# USB.net
KiCad netlist of a schematic drawn in Altium Designer
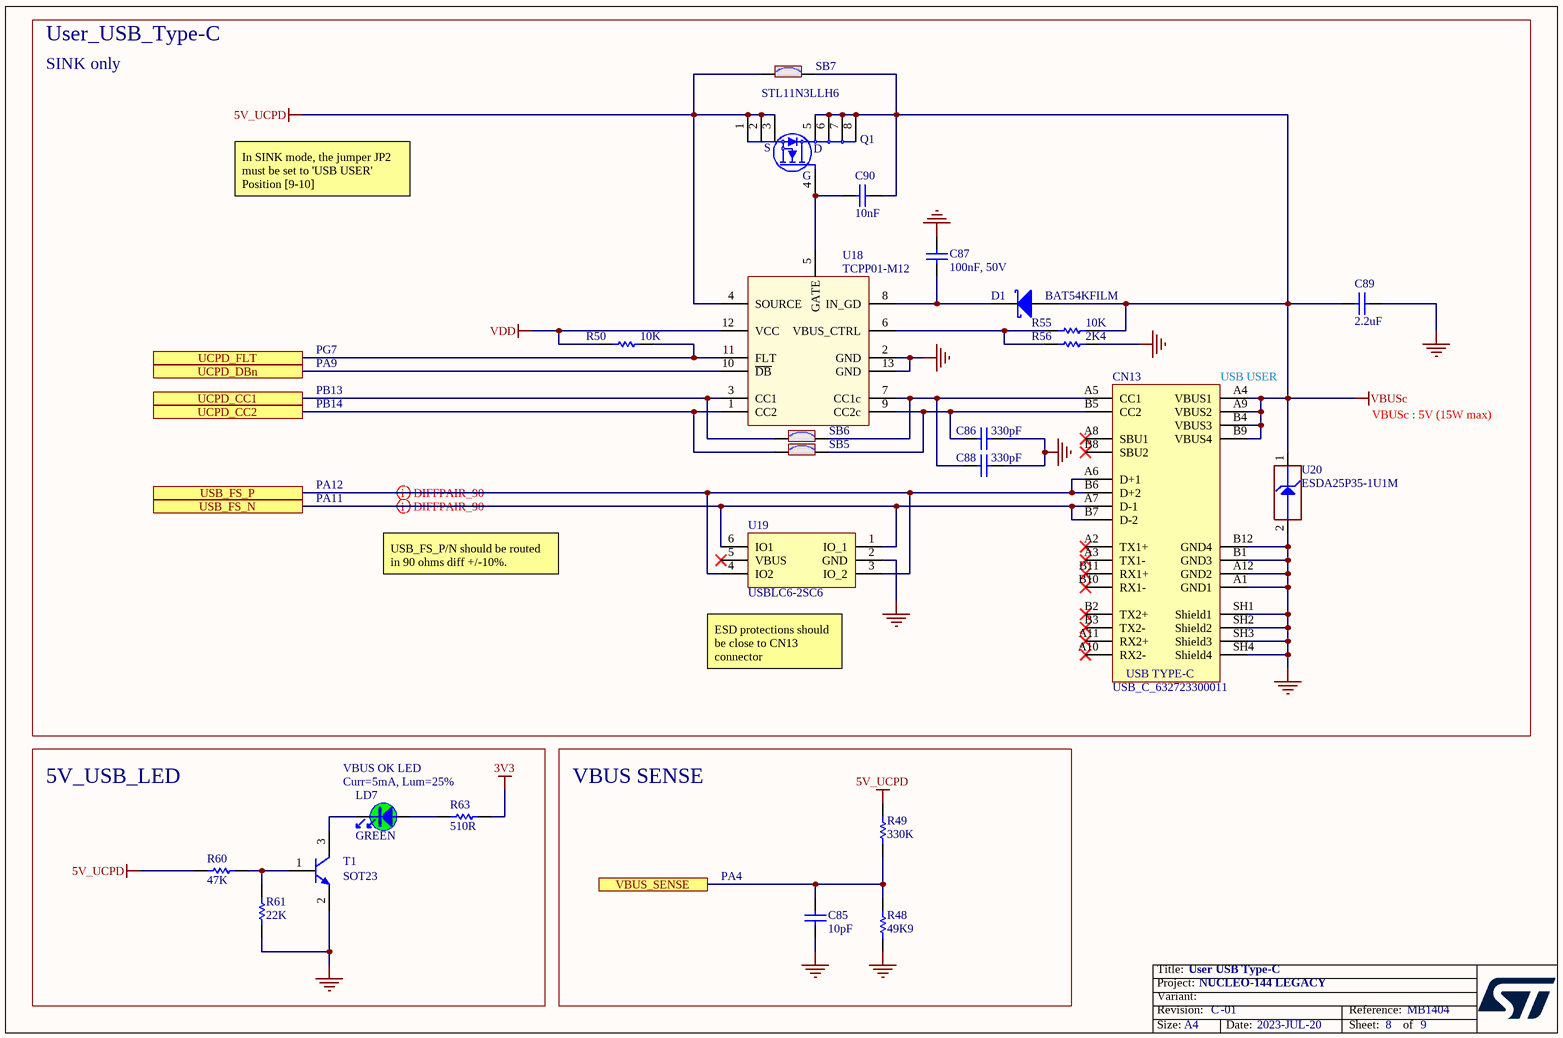
[diagram p0: USB.SchDoc]

(export (version "E")
  (design (tool "Eeschema 10.0.6"))
  (components
    (comp (ref "C85")
      (value "10pF")
      (footprint "MCD_PARTS:C0603")
      (description "Capacitor, MLCC, 10pF, 50V, NPO, 5%, 0603, T=0,8mm")
      (fields
        (field (name "INTERNAL_PART_NUMBER") "MCD-00637")
        (field (name "MANUFACTURER_PART_NUMBER") "CC0603JRNPO9BN100")
        (field (name "PROVIDED_BY") "SUBCO")
      )
      (libsource (lib "MCD_PARTS_database") (part "Capacitor"))
    )
    (comp (ref "C86")
      (value "330pF")
      (footprint "MCD_PARTS:C0402")
      (description "Capacitor, MLCC, 330pF, 50V, NPO, +/-5%, 0402, T=0,5mm")
      (fields (field (name "INTERNAL_PART_NUMBER") "MCD-01579") (field (name "MANUFACTURER") "YAGEO"))
      (libsource (lib "MCD_PARTS_database") (part "Capacitor"))
    )
    (comp (ref "C87")
      (value "100nF, 50V")
      (footprint "MCD_PARTS:C0603")
      (description "Capacitor,100nF,50V,X7R,10%,0603")
      (fields
        (field (name "INTERNAL_PART_NUMBER") "MCD-01099")
        (field (name "MANUFACTURER_PART_NUMBER") "CC0603KRX7R9BB104")
        (field (name "PROVIDED_BY") "SUBCO")
      )
      (libsource (lib "MCD_PARTS_database") (part "Capacitor"))
    )
    (comp (ref "C88")
      (value "330pF")
      (footprint "MCD_PARTS:C0402")
      (description "Capacitor, MLCC, 330pF, 50V, NPO, +/-5%, 0402, T=0,5mm")
      (fields (field (name "INTERNAL_PART_NUMBER") "MCD-01579") (field (name "MANUFACTURER") "YAGEO"))
      (libsource (lib "MCD_PARTS_database") (part "Capacitor"))
    )
    (comp (ref "C89")
      (value "2.2uF")
      (footprint "MCD_PARTS:C0805")
      (description "Capacitor, MLCC, 2.2uF, 25V, X7R, +/-10%, 0805, T=1,25mm")
      (fields (field (name "INTERNAL_PART_NUMBER") "MCD-02372") (field (name "MANUFACTURER") "MURATA"))
      (libsource (lib "MCD_PARTS_database") (part "Capacitor"))
    )
    (comp (ref "C90")
      (value "10nF")
      (footprint "MCD_PARTS:C0402")
      (description "Capacitor, MLCC, 10nF, 50V ,X7R, +/-10%, 0402, T=0.5mm")
      (fields (field (name "INTERNAL_PART_NUMBER") "MCD-02198") (field (name "MANUFACTURER") "YAGEO"))
      (libsource (lib "MCD_PARTS_database") (part "Capacitor"))
    )
    (comp (ref "CN13")
      (value "USB_C_632723300011")
      (footprint "MCD_PARTS:CON_USB-TYPEC_WE_632723300011")
      (description "Connector_USB_TypeC, 24pins, RA, TH, T=1.9mm (USB certified)")
      (fields
        (field (name "INTERNAL_PART_NUMBER") "MCD-02273")
        (field (name "MANUFACTURER") "WURTH ELEKTRONIK")
      )
      (libsource (lib "MCD_PARTS_database") (part "USB_TYPE_C_Receptacle"))
    )
    (comp (ref "D1")
      (value "BAT54KFILM")
      (footprint "MCD_PARTS:DIO_SOD523_1A_2K")
      (description "Small signal Schottky diodes")
      (fields
        (field (name "INTERNAL_PART_NUMBER") "MCD-01677")
        (field (name "MANUFACTURER") "STMICROELECTRONICS")
        (field (name "PROVIDED_BY") "SUBCO")
      )
      (libsource (lib "MCD_PARTS_database") (part "SCHOTTKY_1A_2K"))
    )
    (comp (ref "LD7")
      (value "GREEN")
      (footprint "MCD_PARTS:LED_0603_OSRAM_LG-Q396-PS-35_GREEN_1A2K_H0P4")
      (description "LED Green, 0603 SMD, Forward Voltage Typ=2V, Max=2.5V")
      (fields
        (field (name "INTERNAL_PART_NUMBER") "MCD-00588")
        (field (name "MANUFACTURER_PART_NUMBER") "LG Q396-PS-35")
        (field (name "PROVIDED_BY") "SUBCO")
      )
      (libsource (lib "MCD_PARTS_database") (part "LED_green"))
    )
    (comp (ref "Q1")
      (value "STL11N3LLH6")
      (footprint "MCD_PARTS:MOS_POWERFLAT_3P3X3P3_P065")
      (description "N-channel 30 V, 6 mΩ typ, 11 A STripFET™ H6, Power MOSFET in a PowerFLAT™ 3.3x3.3 package")
      (fields
        (field (name "INTERNAL_PART_NUMBER") "MCD-01810")
        (field (name "MANUFACTURER") "STMICROELECTRONICS")
        (field (name "PROVIDED_BY") "SUBCO with ST control")
      )
      (libsource (lib "MCD_PARTS_database") (part "STL11N3LLH6"))
    )
    (comp (ref "R48")
      (value "49K9")
      (footprint "MCD_PARTS:R0603")
      (description "Resistor,49K9,0603,1%")
      (fields
        (field (name "INTERNAL_PART_NUMBER") "MCD-01171")
        (field (name "MANUFACTURER_PART_NUMBER") "RC0603FR-0749K9L")
        (field (name "PROVIDED_BY") "SUBCO")
      )
      (libsource (lib "MCD_PARTS_database") (part "Resistor"))
    )
    (comp (ref "R49")
      (value "330K")
      (footprint "MCD_PARTS:R0603")
      (description "Resistor,330K,0603,1%,1/10W")
      (fields
        (field (name "INTERNAL_PART_NUMBER") "MCD-00458")
        (field (name "MANUFACTURER_PART_NUMBER") "RC0603FR-07330KL")
        (field (name "PROVIDED_BY") "SUBCO")
      )
      (libsource (lib "MCD_PARTS_database") (part "Resistor"))
    )
    (comp (ref "R50")
      (value "10K")
      (footprint "MCD_PARTS:R0402")
      (description "Resistor,10K,0402,1%,1/16W")
      (fields (field (name "INTERNAL_PART_NUMBER") "MCD-00053") (field (name "BMS_PART_NUMBER") "9131590"))
      (libsource (lib "MCD_PARTS_database") (part "Resistor"))
    )
    (comp (ref "R55")
      (value "10K")
      (footprint "MCD_PARTS:R0402")
      (description "Resistor,10K,0402,1%,1/16W")
      (fields (field (name "INTERNAL_PART_NUMBER") "MCD-00053") (field (name "BMS_PART_NUMBER") "9131590"))
      (libsource (lib "MCD_PARTS_database") (part "Resistor"))
    )
    (comp (ref "R56")
      (value "2K4")
      (footprint "MCD_PARTS:R0402")
      (description "Resistor, 2K4, 0402, +/-1%, 1/16W")
      (fields (field (name "INTERNAL_PART_NUMBER") "MCD-00433") (field (name "MANUFACTURER") "YAGEO"))
      (libsource (lib "MCD_PARTS_database") (part "Resistor"))
    )
    (comp (ref "R60")
      (value "47K")
      (footprint "MCD_PARTS:R0603")
      (description "Resistor,47K,0603,1%,1/10W")
      (fields
        (field (name "INTERNAL_PART_NUMBER") "MCD-00222")
        (field (name "MANUFACTURER_PART_NUMBER") "RC0603FR-0747KL")
        (field (name "PROVIDED_BY") "SUBCO")
      )
      (libsource (lib "MCD_PARTS_database") (part "Resistor"))
    )
    (comp (ref "R61")
      (value "22K")
      (footprint "MCD_PARTS:R0603")
      (description "Resistor,22K,0603,1%,1/10W")
      (fields
        (field (name "INTERNAL_PART_NUMBER") "MCD-00430")
        (field (name "MANUFACTURER_PART_NUMBER") "RC0603FR-0722KL")
        (field (name "PROVIDED_BY") "SUBCO")
      )
      (libsource (lib "MCD_PARTS_database") (part "Resistor"))
    )
    (comp (ref "R63")
      (value "510R")
      (footprint "MCD_PARTS:R0603")
      (description "Resistor,510R,0603,1%,1/10W")
      (fields
        (field (name "INTERNAL_PART_NUMBER") "MCD-00225")
        (field (name "MANUFACTURER_PART_NUMBER") "RC0603FR-07510RL")
        (field (name "PROVIDED_BY") "SUBCO")
      )
      (libsource (lib "MCD_PARTS_database") (part "Resistor"))
    )
    (comp (ref "SB5")
      (value "SB_ON")
      (footprint "MCD_PARTS:SOLDER-BRIDGE_R0402-0R")
      (description "Solder Bridge 0402 ON")
      (fields
        (field (name "INTERNAL_PART_NUMBER") "MCD-01618")
        (field (name "MANUFACTURER_PART_NUMBER") "RC0402JR-070RL")
        (field (name "PROVIDED_BY") "SUBCO")
      )
      (libsource (lib "MCD_PARTS_database") (part "SB_ON"))
    )
    (comp (ref "SB6")
      (value "SB_ON")
      (footprint "MCD_PARTS:SOLDER-BRIDGE_R0402-0R")
      (description "Solder Bridge 0402 ON")
      (fields
        (field (name "INTERNAL_PART_NUMBER") "MCD-01618")
        (field (name "MANUFACTURER_PART_NUMBER") "RC0402JR-070RL")
        (field (name "PROVIDED_BY") "SUBCO")
      )
      (libsource (lib "MCD_PARTS_database") (part "SB_ON"))
    )
    (comp (ref "SB7")
      (value "SB_ON")
      (footprint "MCD_PARTS:SOLDER-BRIDGE_R0402-0R")
      (description "Solder Bridge 0402 ON")
      (fields
        (field (name "INTERNAL_PART_NUMBER") "MCD-01618")
        (field (name "MANUFACTURER_PART_NUMBER") "RC0402JR-070RL")
        (field (name "PROVIDED_BY") "SUBCO")
      )
      (libsource (lib "MCD_PARTS_database") (part "SB_ON"))
    )
    (comp (ref "T1")
      (value "SOT23")
      (footprint "MCD_PARTS:NPN_SOT23")
      (description "NPN Bipolar Transistor")
      (fields
        (field (name "INTERNAL_PART_NUMBER") "MCD-00073")
        (field (name "MANUFACTURER_PART_NUMBER") "BSR14")
        (field (name "PROVIDED_BY") "SUBCO")
      )
      (libsource (lib "MCD_PARTS_database") (part "9013-SOT23"))
    )
    (comp (ref "U18")
      (value "TCPP01-M12")
      (footprint "MCD_PARTS:ICC_QFN12L-EPAD_3X3_P050")
      (description "USB Type-C Port Protection for USB Power Delivery, PPS compliant")
      (fields
        (field (name "INTERNAL_PART_NUMBER") "MCD-01809")
        (field (name "MANUFACTURER") "STMICROELECTRONICS")
        (field (name "PROVIDED_BY") "SUBCO with ST control")
      )
      (libsource (lib "MCD_PARTS_database") (part "TCPP01-M12"))
    )
    (comp (ref "U19")
      (value "USBLC6-2SC6")
      (footprint "MCD_PARTS:ESD_SOT23-6L")
      (description "Very low capacitance ESD protection")
      (fields
        (field (name "INTERNAL_PART_NUMBER") "MCD-00163")
        (field (name "MANUFACTURER") "STMICROELECTRONICS")
        (field (name "PROVIDED_BY") "SUBCO with ST control")
      )
      (libsource (lib "MCD_PARTS_database") (part "USBLC6-2SC6"))
    )
    (comp (ref "U20")
      (value "ESDA25P35-1U1M")
      (footprint "MCD_PARTS:ESD_QFN1610_2N_1K_2A")
      (description "High power Transient voltage suppressor:25V/35A EOS and ESD transients protection.")
      (fields
        (field (name "INTERNAL_PART_NUMBER") "MCD-01207")
        (field (name "MANUFACTURER") "STMICROELECTRONICS")
        (field (name "PROVIDED_BY") "SUBCO with ST control")
      )
      (libsource (lib "MCD_PARTS_database") (part "ESD-TRANSIL"))
    )
  )
  (nets
    (net (code "1") (name "/UCPD_CC1") (class "Default")
      (node (ref "SB6") (pin "1") (pinfunction "1_1") (pintype "passive"))
      (node (ref "U18") (pin "3") (pinfunction "CC1_3") (pintype "passive"))
    )
    (net (code "2") (name "/UCPD_CC2") (class "Default")
      (node (ref "SB5") (pin "1") (pinfunction "1_1") (pintype "passive"))
      (node (ref "U18") (pin "1") (pinfunction "CC2_1") (pintype "passive"))
    )
    (net (code "3") (name "/UCPD_DBn") (class "Default")
      (node (ref "U18") (pin "10") (pinfunction "~{DB}_10") (pintype "passive"))
    )
    (net (code "4") (name "/UCPD_FLT") (class "Default")
      (node (ref "R50") (pin "2") (pinfunction "2_2") (pintype "passive"))
      (node (ref "U18") (pin "11") (pinfunction "FLT_11") (pintype "passive"))
    )
    (net (code "5") (name "/USB_FS_N") (class "Default")
      (node (ref "CN13") (pin "A7") (pinfunction "D-1_A7") (pintype "passive"))
      (node (ref "CN13") (pin "B7") (pinfunction "D-2_B7") (pintype "passive"))
      (node (ref "U19") (pin "1") (pinfunction "IO_1_1") (pintype "passive"))
      (node (ref "U19") (pin "6") (pinfunction "IO1_6") (pintype "passive"))
    )
    (net (code "6") (name "/USB_FS_P") (class "Default")
      (node (ref "CN13") (pin "A6") (pinfunction "D+1_A6") (pintype "passive"))
      (node (ref "CN13") (pin "B6") (pinfunction "D+2_B6") (pintype "passive"))
      (node (ref "U19") (pin "3") (pinfunction "IO_2_3") (pintype "passive"))
      (node (ref "U19") (pin "4") (pinfunction "IO2_4") (pintype "passive"))
    )
    (net (code "7") (name "/VBUS_SENSE") (class "Default")
      (node (ref "C85") (pin "2") (pinfunction "2_2") (pintype "passive"))
      (node (ref "R48") (pin "2") (pinfunction "2_2") (pintype "passive"))
      (node (ref "R49") (pin "1") (pinfunction "1_1") (pintype "passive"))
    )
    (net (code "8") (name "3V3") (class "Default")
      (node (ref "R63") (pin "2") (pinfunction "2_2") (pintype "passive"))
    )
    (net (code "9") (name "5V_UCPD") (class "Default")
      (node (ref "Q1") (pin "1") (pinfunction "S_1") (pintype "passive"))
      (node (ref "Q1") (pin "2") (pinfunction "S_2") (pintype "passive"))
      (node (ref "Q1") (pin "3") (pinfunction "S_3") (pintype "passive"))
      (node (ref "R49") (pin "2") (pinfunction "2_2") (pintype "passive"))
      (node (ref "R60") (pin "1") (pinfunction "1_1") (pintype "passive"))
      (node (ref "SB7") (pin "1") (pinfunction "1_1") (pintype "passive"))
      (node (ref "U18") (pin "4") (pinfunction "SOURCE_4") (pintype "passive"))
    )
    (net (code "10") (name "GND") (class "Default")
      (node (ref "C85") (pin "1") (pinfunction "1_1") (pintype "passive"))
      (node (ref "C86") (pin "2") (pinfunction "2_2") (pintype "passive"))
      (node (ref "C87") (pin "2") (pinfunction "2_2") (pintype "passive"))
      (node (ref "C88") (pin "2") (pinfunction "2_2") (pintype "passive"))
      (node (ref "C89") (pin "2") (pinfunction "2_2") (pintype "passive"))
      (node (ref "CN13") (pin "A1") (pinfunction "GND1_A1") (pintype "passive"))
      (node (ref "CN13") (pin "A12") (pinfunction "GND2_A12") (pintype "passive"))
      (node (ref "CN13") (pin "B1") (pinfunction "GND3_B1") (pintype "passive"))
      (node (ref "CN13") (pin "B12") (pinfunction "GND4_B12") (pintype "passive"))
      (node (ref "CN13") (pin "SH1") (pinfunction "Shield1_SH1") (pintype "passive"))
      (node (ref "CN13") (pin "SH2") (pinfunction "Shield2_SH2") (pintype "passive"))
      (node (ref "CN13") (pin "SH3") (pinfunction "Shield3_SH3") (pintype "passive"))
      (node (ref "CN13") (pin "SH4") (pinfunction "Shield4_SH4") (pintype "passive"))
      (node (ref "R48") (pin "1") (pinfunction "1_1") (pintype "passive"))
      (node (ref "R56") (pin "2") (pinfunction "2_2") (pintype "passive"))
      (node (ref "R61") (pin "1") (pinfunction "1_1") (pintype "passive"))
      (node (ref "T1") (pin "2") (pinfunction "E_2") (pintype "passive"))
      (node (ref "U18") (pin "13") (pinfunction "GND_13") (pintype "passive"))
      (node (ref "U18") (pin "2") (pinfunction "GND_2") (pintype "passive"))
      (node (ref "U19") (pin "2") (pinfunction "GND_2") (pintype "passive"))
      (node (ref "U20") (pin "2") (pinfunction "GND_2") (pintype "passive"))
    )
    (net (code "11") (name "Net-(CN13-CC1)") (class "Default")
      (node (ref "C88") (pin "1") (pinfunction "1_1") (pintype "passive"))
      (node (ref "CN13") (pin "A5") (pinfunction "CC1_A5") (pintype "passive"))
      (node (ref "SB6") (pin "2") (pinfunction "2_2") (pintype "passive"))
      (node (ref "U18") (pin "7") (pinfunction "CC1c_7") (pintype "passive"))
    )
    (net (code "12") (name "Net-(CN13-CC2)") (class "Default")
      (node (ref "C86") (pin "1") (pinfunction "1_1") (pintype "passive"))
      (node (ref "CN13") (pin "B5") (pinfunction "CC2_B5") (pintype "passive"))
      (node (ref "SB5") (pin "2") (pinfunction "2_2") (pintype "passive"))
      (node (ref "U18") (pin "9") (pinfunction "CC2c_9") (pintype "passive"))
    )
    (net (code "13") (name "Net-(D1-K)") (class "Default")
      (node (ref "C87") (pin "1") (pinfunction "1_1") (pintype "passive"))
      (node (ref "D1") (pin "2") (pinfunction "K_2") (pintype "passive"))
      (node (ref "U18") (pin "8") (pinfunction "IN_GD_8") (pintype "passive"))
    )
    (net (code "14") (name "Net-(LD7-Pad1)") (class "Default")
      (node (ref "LD7") (pin "1") (pintype "passive"))
      (node (ref "R63") (pin "1") (pinfunction "1_1") (pintype "passive"))
    )
    (net (code "15") (name "Net-(Q1-G)") (class "Default")
      (node (ref "C90") (pin "1") (pinfunction "1_1") (pintype "passive"))
      (node (ref "Q1") (pin "4") (pinfunction "G_4") (pintype "passive"))
      (node (ref "U18") (pin "5") (pinfunction "GATE_5") (pintype "passive"))
    )
    (net (code "16") (name "Net-(T1-B)") (class "Default")
      (node (ref "R60") (pin "2") (pinfunction "2_2") (pintype "passive"))
      (node (ref "R61") (pin "2") (pinfunction "2_2") (pintype "passive"))
      (node (ref "T1") (pin "1") (pinfunction "B_1") (pintype "passive"))
    )
    (net (code "17") (name "Net-(T1-C)") (class "Default")
      (node (ref "LD7") (pin "2") (pintype "passive"))
      (node (ref "T1") (pin "3") (pinfunction "C_3") (pintype "passive"))
    )
    (net (code "18") (name "Net-(U18-VBUS_CTRL)") (class "Default")
      (node (ref "R55") (pin "1") (pinfunction "1_1") (pintype "passive"))
      (node (ref "R56") (pin "1") (pinfunction "1_1") (pintype "passive"))
      (node (ref "U18") (pin "6") (pinfunction "VBUS_CTRL_6") (pintype "passive"))
    )
    (net (code "19") (name "VBUSc") (class "Default")
      (node (ref "C89") (pin "1") (pinfunction "1_1") (pintype "passive"))
      (node (ref "C90") (pin "2") (pinfunction "2_2") (pintype "passive"))
      (node (ref "CN13") (pin "A4") (pinfunction "VBUS1_A4") (pintype "passive"))
      (node (ref "CN13") (pin "A9") (pinfunction "VBUS2_A9") (pintype "passive"))
      (node (ref "CN13") (pin "B4") (pinfunction "VBUS3_B4") (pintype "passive"))
      (node (ref "CN13") (pin "B9") (pinfunction "VBUS4_B9") (pintype "passive"))
      (node (ref "D1") (pin "1") (pinfunction "A_1") (pintype "passive"))
      (node (ref "Q1") (pin "5") (pinfunction "D_5") (pintype "passive"))
      (node (ref "Q1") (pin "6") (pinfunction "D_6") (pintype "passive"))
      (node (ref "Q1") (pin "7") (pinfunction "D_7") (pintype "passive"))
      (node (ref "Q1") (pin "8") (pinfunction "D_8") (pintype "passive"))
      (node (ref "R55") (pin "2") (pinfunction "2_2") (pintype "passive"))
      (node (ref "SB7") (pin "2") (pinfunction "2_2") (pintype "passive"))
      (node (ref "U20") (pin "1") (pinfunction "IO1_1") (pintype "passive"))
    )
    (net (code "20") (name "VDD") (class "Default")
      (node (ref "R50") (pin "1") (pinfunction "1_1") (pintype "passive"))
      (node (ref "U18") (pin "12") (pinfunction "VCC_12") (pintype "passive"))
    )
    (net (code "21") (name "unconnected-(CN13-RX1+-PadB11)") (class "Default")
      (node (ref "CN13") (pin "B11") (pinfunction "RX1+_B11") (pintype "passive+no_connect"))
    )
    (net (code "22") (name "unconnected-(CN13-RX1--PadB10)") (class "Default")
      (node (ref "CN13") (pin "B10") (pinfunction "RX1-_B10") (pintype "passive+no_connect"))
    )
    (net (code "23") (name "unconnected-(CN13-RX2+-PadA11)") (class "Default")
      (node (ref "CN13") (pin "A11") (pinfunction "RX2+_A11") (pintype "passive+no_connect"))
    )
    (net (code "24") (name "unconnected-(CN13-RX2--PadA10)") (class "Default")
      (node (ref "CN13") (pin "A10") (pinfunction "RX2-_A10") (pintype "passive+no_connect"))
    )
    (net (code "25") (name "unconnected-(CN13-SBU1-PadA8)") (class "Default")
      (node (ref "CN13") (pin "A8") (pinfunction "SBU1_A8") (pintype "passive+no_connect"))
    )
    (net (code "26") (name "unconnected-(CN13-SBU2-PadB8)") (class "Default")
      (node (ref "CN13") (pin "B8") (pinfunction "SBU2_B8") (pintype "passive+no_connect"))
    )
    (net (code "27") (name "unconnected-(CN13-TX1+-PadA2)") (class "Default")
      (node (ref "CN13") (pin "A2") (pinfunction "TX1+_A2") (pintype "passive+no_connect"))
    )
    (net (code "28") (name "unconnected-(CN13-TX1--PadA3)") (class "Default")
      (node (ref "CN13") (pin "A3") (pinfunction "TX1-_A3") (pintype "passive+no_connect"))
    )
    (net (code "29") (name "unconnected-(CN13-TX2+-PadB2)") (class "Default")
      (node (ref "CN13") (pin "B2") (pinfunction "TX2+_B2") (pintype "passive+no_connect"))
    )
    (net (code "30") (name "unconnected-(CN13-TX2--PadB3)") (class "Default")
      (node (ref "CN13") (pin "B3") (pinfunction "TX2-_B3") (pintype "passive+no_connect"))
    )
    (net (code "31") (name "unconnected-(U19-VBUS-Pad5)") (class "Default")
      (node (ref "U19") (pin "5") (pinfunction "VBUS_5") (pintype "passive+no_connect"))
    )
  )
)
